# Load_Cells_SCH.net
KiCad netlist of a schematic drawn in Altium Designer
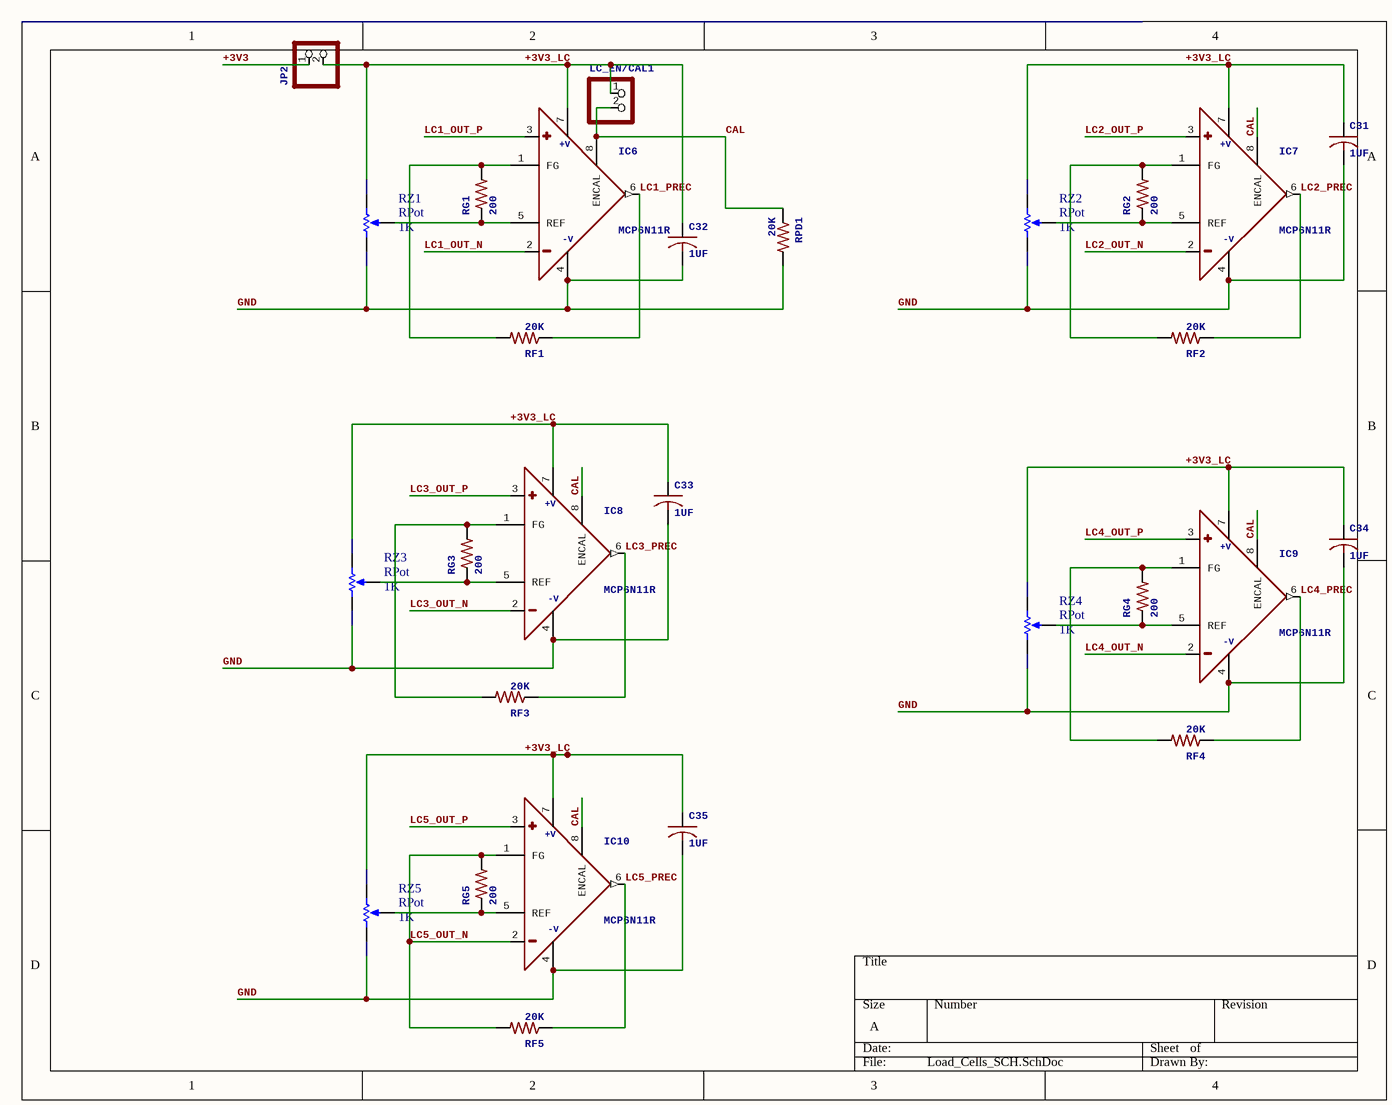
[diagram p0: Load_Cells_SCH.SchDoc]

(export (version "E")
  (design (tool "Eeschema 10.0.6"))
  (components
    (comp (ref "C31")
      (value "1UF")
      (footprint "CAPCP2012X06N")
      (description "CAPACITOR, American symbol")
      (libsource (lib "rcl") (part "C-USC0805"))
    )
    (comp (ref "C32")
      (value "1UF")
      (footprint "CAPCP2012X06N")
      (description "CAPACITOR, American symbol")
      (libsource (lib "rcl") (part "C-USC0805"))
    )
    (comp (ref "C33")
      (value "1UF")
      (footprint "CAPCP2012X06N")
      (description "CAPACITOR, American symbol")
      (libsource (lib "rcl") (part "C-USC0805"))
    )
    (comp (ref "C34")
      (value "1UF")
      (footprint "CAPCP2012X06N")
      (description "CAPACITOR, American symbol")
      (libsource (lib "rcl") (part "C-USC0805"))
    )
    (comp (ref "C35")
      (value "1UF")
      (footprint "CAPCP2012X06N")
      (description "CAPACITOR, American symbol")
      (libsource (lib "rcl") (part "C-USC0805"))
    )
    (comp (ref "IC6")
      (value "MCP6N11R")
      (footprint "SOIC127P1030X265-8N")
      (fields
        (field (name "MPN") "AD620AR")
        (field (name "+V") "+V")
        (field (name "-V") "-V")
        (field (name "LIBRARYNAME") "microchip-extra")
      )
      (libsource (lib "microchip-extra") (part "MCP6N11R"))
    )
    (comp (ref "IC7")
      (value "MCP6N11R")
      (footprint "SOIC127P1030X265-8N")
      (fields
        (field (name "MPN") "AD620AR")
        (field (name "+V") "+V")
        (field (name "-V") "-V")
        (field (name "LIBRARYNAME") "microchip-extra")
      )
      (libsource (lib "microchip-extra") (part "MCP6N11R"))
    )
    (comp (ref "IC8")
      (value "MCP6N11R")
      (footprint "SOIC127P1030X265-8N")
      (fields
        (field (name "MPN") "AD620AR")
        (field (name "+V") "+V")
        (field (name "-V") "-V")
        (field (name "LIBRARYNAME") "microchip-extra")
      )
      (libsource (lib "microchip-extra") (part "MCP6N11R"))
    )
    (comp (ref "IC9")
      (value "MCP6N11R")
      (footprint "SOIC127P1030X265-8N")
      (fields
        (field (name "MPN") "AD620AR")
        (field (name "+V") "+V")
        (field (name "-V") "-V")
        (field (name "LIBRARYNAME") "microchip-extra")
      )
      (libsource (lib "microchip-extra") (part "MCP6N11R"))
    )
    (comp (ref "IC10")
      (value "MCP6N11R")
      (footprint "SOIC127P1030X265-8N")
      (fields
        (field (name "MPN") "AD620AR")
        (field (name "+V") "+V")
        (field (name "-V") "-V")
        (field (name "LIBRARYNAME") "microchip-extra")
      )
      (libsource (lib "microchip-extra") (part "MCP6N11R"))
    )
    (comp (ref "JP2")
      (value "PINHD-1X2")
      (footprint "MHDR1X2")
      (description "PIN HEADER")
      (fields (field (name "LIBRARYNAME") "pinhead"))
      (libsource (lib "pinhead") (part "PINHD-1X2"))
    )
    (comp (ref "LC_EN/CAL1")
      (value "PINHD-1X2")
      (footprint "MHDR1X2")
      (description "PIN HEADER")
      (fields (field (name "LIBRARYNAME") "pinhead"))
      (libsource (lib "pinhead") (part "PINHD-1X2"))
    )
    (comp (ref "RF1")
      (value "20K")
      (footprint "RESC_0805_2012")
      (description "RESISTOR, American symbol")
      (libsource (lib "rcl") (part "R-US_R0805"))
    )
    (comp (ref "RF2")
      (value "20K")
      (footprint "RESC_0805_2012")
      (description "RESISTOR, American symbol")
      (libsource (lib "rcl") (part "R-US_R0805"))
    )
    (comp (ref "RF3")
      (value "20K")
      (footprint "RESC_0805_2012")
      (description "RESISTOR, American symbol")
      (libsource (lib "rcl") (part "R-US_R0805"))
    )
    (comp (ref "RF4")
      (value "20K")
      (footprint "RESC_0805_2012")
      (description "RESISTOR, American symbol")
      (libsource (lib "rcl") (part "R-US_R0805"))
    )
    (comp (ref "RF5")
      (value "20K")
      (footprint "RESC_0805_2012")
      (description "RESISTOR, American symbol")
      (libsource (lib "rcl") (part "R-US_R0805"))
    )
    (comp (ref "RG1")
      (value "200")
      (footprint "RESC_0805_2012")
      (description "RESISTOR, American symbol")
      (libsource (lib "rcl") (part "R-US_R0805"))
    )
    (comp (ref "RG2")
      (value "200")
      (footprint "RESC_0805_2012")
      (description "RESISTOR, American symbol")
      (libsource (lib "rcl") (part "R-US_R0805"))
    )
    (comp (ref "RG3")
      (value "200")
      (footprint "RESC_0805_2012")
      (description "RESISTOR, American symbol")
      (libsource (lib "rcl") (part "R-US_R0805"))
    )
    (comp (ref "RG4")
      (value "200")
      (footprint "RESC_0805_2012")
      (description "RESISTOR, American symbol")
      (libsource (lib "rcl") (part "R-US_R0805"))
    )
    (comp (ref "RG5")
      (value "200")
      (footprint "RESC_0805_2012")
      (description "RESISTOR, American symbol")
      (libsource (lib "rcl") (part "R-US_R0805"))
    )
    (comp (ref "RPD1")
      (value "20K")
      (footprint "RESC_0805_2012")
      (description "RESISTOR, American symbol")
      (libsource (lib "rcl") (part "R-US_R0805"))
    )
    (comp (ref "RZ1")
      (value "RPot")
      (footprint "VR5")
      (description "Potentiometer")
      (fields (field (name "ALTIUM_VALUE") "1K") (field (name "PUBLISHER") "Altium Limited"))
      (libsource (lib "Miscellaneous Devices") (part "RPot"))
    )
    (comp (ref "RZ2")
      (value "RPot")
      (footprint "VR5")
      (description "Potentiometer")
      (fields (field (name "ALTIUM_VALUE") "1K") (field (name "PUBLISHER") "Altium Limited"))
      (libsource (lib "Miscellaneous Devices") (part "RPot"))
    )
    (comp (ref "RZ3")
      (value "RPot")
      (footprint "VR5")
      (description "Potentiometer")
      (fields (field (name "ALTIUM_VALUE") "1K") (field (name "PUBLISHER") "Altium Limited"))
      (libsource (lib "Miscellaneous Devices") (part "RPot"))
    )
    (comp (ref "RZ4")
      (value "RPot")
      (footprint "VR5")
      (description "Potentiometer")
      (fields (field (name "ALTIUM_VALUE") "1K") (field (name "PUBLISHER") "Altium Limited"))
      (libsource (lib "Miscellaneous Devices") (part "RPot"))
    )
    (comp (ref "RZ5")
      (value "RPot")
      (footprint "VR5")
      (description "Potentiometer")
      (fields (field (name "ALTIUM_VALUE") "1K") (field (name "PUBLISHER") "Altium Limited"))
      (libsource (lib "Miscellaneous Devices") (part "RPot"))
    )
  )
  (nets
    (net (code "1") (name "/+3V3") (class "Default")
      (node (ref "JP2") (pin "1") (pinfunction "1_1") (pintype "passive"))
    )
    (net (code "2") (name "/+3V3_LC") (class "Default")
      (node (ref "C31") (pin "1") (pinfunction "1_1") (pintype "passive"))
      (node (ref "C32") (pin "1") (pinfunction "1_1") (pintype "passive"))
      (node (ref "C33") (pin "1") (pinfunction "1_1") (pintype "passive"))
      (node (ref "C34") (pin "1") (pinfunction "1_1") (pintype "passive"))
      (node (ref "C35") (pin "1") (pinfunction "1_1") (pintype "passive"))
      (node (ref "IC10") (pin "7") (pinfunction "+V_7") (pintype "power_in"))
      (node (ref "IC6") (pin "7") (pinfunction "+V_7") (pintype "power_in"))
      (node (ref "IC7") (pin "7") (pinfunction "+V_7") (pintype "power_in"))
      (node (ref "IC8") (pin "7") (pinfunction "+V_7") (pintype "power_in"))
      (node (ref "IC9") (pin "7") (pinfunction "+V_7") (pintype "power_in"))
      (node (ref "JP2") (pin "2") (pinfunction "2_2") (pintype "passive"))
      (node (ref "LC_EN/CAL1") (pin "1") (pinfunction "1_1") (pintype "passive"))
      (node (ref "RZ1") (pin "2") (pinfunction "BOT_2") (pintype "passive"))
      (node (ref "RZ2") (pin "2") (pinfunction "BOT_2") (pintype "passive"))
      (node (ref "RZ3") (pin "2") (pinfunction "BOT_2") (pintype "passive"))
      (node (ref "RZ4") (pin "2") (pinfunction "BOT_2") (pintype "passive"))
      (node (ref "RZ5") (pin "2") (pinfunction "BOT_2") (pintype "passive"))
    )
    (net (code "3") (name "/CAL") (class "Default")
      (node (ref "IC10") (pin "8") (pinfunction "ENCAL_8") (pintype "passive"))
      (node (ref "IC6") (pin "8") (pinfunction "ENCAL_8") (pintype "passive"))
      (node (ref "IC7") (pin "8") (pinfunction "ENCAL_8") (pintype "passive"))
      (node (ref "IC8") (pin "8") (pinfunction "ENCAL_8") (pintype "passive"))
      (node (ref "IC9") (pin "8") (pinfunction "ENCAL_8") (pintype "passive"))
      (node (ref "LC_EN/CAL1") (pin "2") (pinfunction "2_2") (pintype "passive"))
      (node (ref "RPD1") (pin "1") (pinfunction "1_1") (pintype "passive"))
    )
    (net (code "4") (name "/GND") (class "Default")
      (node (ref "C31") (pin "2") (pinfunction "2_2") (pintype "passive"))
      (node (ref "C32") (pin "2") (pinfunction "2_2") (pintype "passive"))
      (node (ref "C33") (pin "2") (pinfunction "2_2") (pintype "passive"))
      (node (ref "C34") (pin "2") (pinfunction "2_2") (pintype "passive"))
      (node (ref "C35") (pin "2") (pinfunction "2_2") (pintype "passive"))
      (node (ref "IC10") (pin "4") (pinfunction "-V_4") (pintype "power_in"))
      (node (ref "IC6") (pin "4") (pinfunction "-V_4") (pintype "power_in"))
      (node (ref "IC7") (pin "4") (pinfunction "-V_4") (pintype "power_in"))
      (node (ref "IC8") (pin "4") (pinfunction "-V_4") (pintype "power_in"))
      (node (ref "IC9") (pin "4") (pinfunction "-V_4") (pintype "power_in"))
      (node (ref "RPD1") (pin "2") (pinfunction "2_2") (pintype "passive"))
      (node (ref "RZ1") (pin "1") (pinfunction "TOP_1") (pintype "passive"))
      (node (ref "RZ2") (pin "1") (pinfunction "TOP_1") (pintype "passive"))
      (node (ref "RZ3") (pin "1") (pinfunction "TOP_1") (pintype "passive"))
      (node (ref "RZ4") (pin "1") (pinfunction "TOP_1") (pintype "passive"))
      (node (ref "RZ5") (pin "1") (pinfunction "TOP_1") (pintype "passive"))
    )
    (net (code "5") (name "/LC1_OUT_N") (class "Default")
      (node (ref "IC6") (pin "2") (pinfunction "-_2") (pintype "passive"))
    )
    (net (code "6") (name "/LC1_OUT_P") (class "Default")
      (node (ref "IC6") (pin "3") (pinfunction "+_3") (pintype "passive"))
    )
    (net (code "7") (name "/LC1_PREC") (class "Default")
      (node (ref "IC6") (pin "6") (pinfunction "OUT_6") (pintype "output"))
      (node (ref "RF1") (pin "1") (pinfunction "1_1") (pintype "passive"))
    )
    (net (code "8") (name "/LC2_OUT_N") (class "Default")
      (node (ref "IC7") (pin "2") (pinfunction "-_2") (pintype "passive"))
    )
    (net (code "9") (name "/LC2_OUT_P") (class "Default")
      (node (ref "IC7") (pin "3") (pinfunction "+_3") (pintype "passive"))
    )
    (net (code "10") (name "/LC2_PREC") (class "Default")
      (node (ref "IC7") (pin "6") (pinfunction "OUT_6") (pintype "output"))
      (node (ref "RF2") (pin "1") (pinfunction "1_1") (pintype "passive"))
    )
    (net (code "11") (name "/LC3_OUT_N") (class "Default")
      (node (ref "IC8") (pin "2") (pinfunction "-_2") (pintype "passive"))
    )
    (net (code "12") (name "/LC3_OUT_P") (class "Default")
      (node (ref "IC8") (pin "3") (pinfunction "+_3") (pintype "passive"))
    )
    (net (code "13") (name "/LC3_PREC") (class "Default")
      (node (ref "IC8") (pin "6") (pinfunction "OUT_6") (pintype "output"))
      (node (ref "RF3") (pin "1") (pinfunction "1_1") (pintype "passive"))
    )
    (net (code "14") (name "/LC4_OUT_N") (class "Default")
      (node (ref "IC9") (pin "2") (pinfunction "-_2") (pintype "passive"))
    )
    (net (code "15") (name "/LC4_OUT_P") (class "Default")
      (node (ref "IC9") (pin "3") (pinfunction "+_3") (pintype "passive"))
    )
    (net (code "16") (name "/LC4_PREC") (class "Default")
      (node (ref "IC9") (pin "6") (pinfunction "OUT_6") (pintype "output"))
      (node (ref "RF4") (pin "1") (pinfunction "1_1") (pintype "passive"))
    )
    (net (code "17") (name "/LC5_OUT_N") (class "Default")
      (node (ref "IC10") (pin "1") (pinfunction "FG_1") (pintype "passive"))
      (node (ref "IC10") (pin "2") (pinfunction "-_2") (pintype "passive"))
      (node (ref "RF5") (pin "2") (pinfunction "2_2") (pintype "passive"))
      (node (ref "RG5") (pin "2") (pinfunction "2_2") (pintype "passive"))
    )
    (net (code "18") (name "/LC5_OUT_P") (class "Default")
      (node (ref "IC10") (pin "3") (pinfunction "+_3") (pintype "passive"))
    )
    (net (code "19") (name "/LC5_PREC") (class "Default")
      (node (ref "IC10") (pin "6") (pinfunction "OUT_6") (pintype "output"))
      (node (ref "RF5") (pin "1") (pinfunction "1_1") (pintype "passive"))
    )
    (net (code "20") (name "Net-(IC6-FG)") (class "Default")
      (node (ref "IC6") (pin "1") (pinfunction "FG_1") (pintype "passive"))
      (node (ref "RF1") (pin "2") (pinfunction "2_2") (pintype "passive"))
      (node (ref "RG1") (pin "2") (pinfunction "2_2") (pintype "passive"))
    )
    (net (code "21") (name "Net-(IC6-REF)") (class "Default")
      (node (ref "IC6") (pin "5") (pinfunction "REF_5") (pintype "passive"))
      (node (ref "RG1") (pin "1") (pinfunction "1_1") (pintype "passive"))
      (node (ref "RZ1") (pin "3") (pinfunction "TAP_3") (pintype "passive"))
    )
    (net (code "22") (name "Net-(IC7-FG)") (class "Default")
      (node (ref "IC7") (pin "1") (pinfunction "FG_1") (pintype "passive"))
      (node (ref "RF2") (pin "2") (pinfunction "2_2") (pintype "passive"))
      (node (ref "RG2") (pin "2") (pinfunction "2_2") (pintype "passive"))
    )
    (net (code "23") (name "Net-(IC7-REF)") (class "Default")
      (node (ref "IC7") (pin "5") (pinfunction "REF_5") (pintype "passive"))
      (node (ref "RG2") (pin "1") (pinfunction "1_1") (pintype "passive"))
      (node (ref "RZ2") (pin "3") (pinfunction "TAP_3") (pintype "passive"))
    )
    (net (code "24") (name "Net-(IC8-FG)") (class "Default")
      (node (ref "IC8") (pin "1") (pinfunction "FG_1") (pintype "passive"))
      (node (ref "RF3") (pin "2") (pinfunction "2_2") (pintype "passive"))
      (node (ref "RG3") (pin "2") (pinfunction "2_2") (pintype "passive"))
    )
    (net (code "25") (name "Net-(IC8-REF)") (class "Default")
      (node (ref "IC8") (pin "5") (pinfunction "REF_5") (pintype "passive"))
      (node (ref "RG3") (pin "1") (pinfunction "1_1") (pintype "passive"))
      (node (ref "RZ3") (pin "3") (pinfunction "TAP_3") (pintype "passive"))
    )
    (net (code "26") (name "Net-(IC9-FG)") (class "Default")
      (node (ref "IC9") (pin "1") (pinfunction "FG_1") (pintype "passive"))
      (node (ref "RF4") (pin "2") (pinfunction "2_2") (pintype "passive"))
      (node (ref "RG4") (pin "2") (pinfunction "2_2") (pintype "passive"))
    )
    (net (code "27") (name "Net-(IC9-REF)") (class "Default")
      (node (ref "IC9") (pin "5") (pinfunction "REF_5") (pintype "passive"))
      (node (ref "RG4") (pin "1") (pinfunction "1_1") (pintype "passive"))
      (node (ref "RZ4") (pin "3") (pinfunction "TAP_3") (pintype "passive"))
    )
    (net (code "28") (name "Net-(IC10-REF)") (class "Default")
      (node (ref "IC10") (pin "5") (pinfunction "REF_5") (pintype "passive"))
      (node (ref "RG5") (pin "1") (pinfunction "1_1") (pintype "passive"))
      (node (ref "RZ5") (pin "3") (pinfunction "TAP_3") (pintype "passive"))
    )
  )
)
